# SingleDriver.net
KiCad netlist of a schematic drawn in Altium Designer
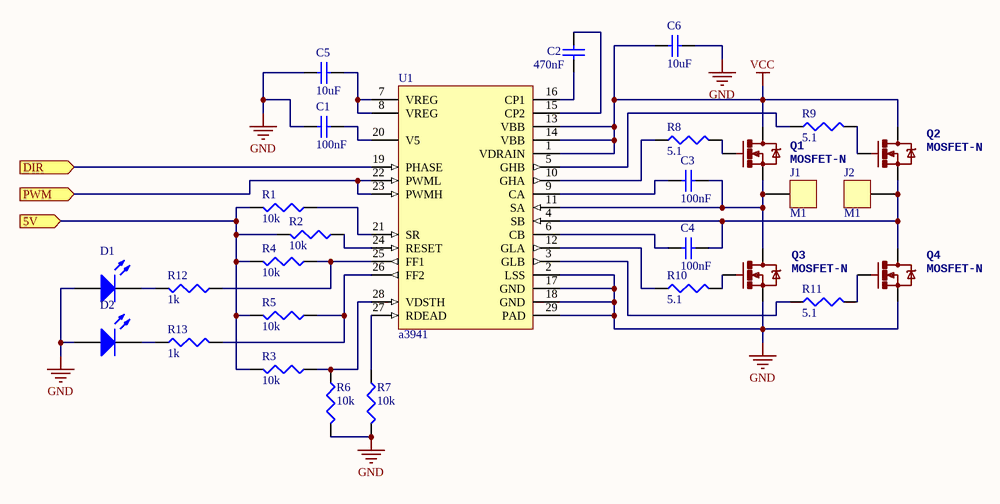
[diagram p0: SingleDriver.SchDoc]

(export (version "E")
  (design (tool "Eeschema 10.0.6"))
  (components
    (comp (ref "C1")
      (value "100nF")
      (footprint "1608[0603]")
      (description "Capacitor (Semiconductor SIM Model)")
      (fields (field (name "PUBLISHER") "Altium Limited"))
      (libsource (lib "Miscellaneous Devices") (part "Cap Semi"))
    )
    (comp (ref "C2")
      (value "470nF")
      (footprint "1608[0603]")
      (description "Capacitor (Semiconductor SIM Model)")
      (fields (field (name "PUBLISHER") "Altium Limited"))
      (libsource (lib "Miscellaneous Devices") (part "Cap Semi"))
    )
    (comp (ref "C3")
      (value "100nF")
      (footprint "1608[0603]")
      (description "Capacitor (Semiconductor SIM Model)")
      (fields (field (name "PUBLISHER") "Altium Limited"))
      (libsource (lib "Miscellaneous Devices") (part "Cap Semi"))
    )
    (comp (ref "C4")
      (value "100nF")
      (footprint "1608[0603]")
      (description "Capacitor (Semiconductor SIM Model)")
      (fields (field (name "PUBLISHER") "Altium Limited"))
      (libsource (lib "Miscellaneous Devices") (part "Cap Semi"))
    )
    (comp (ref "C5")
      (value "10uF")
      (footprint "C1206")
      (description "Capacitor (Semiconductor SIM Model)")
      (fields (field (name "PUBLISHER") "Altium Limited"))
      (libsource (lib "Miscellaneous Devices") (part "Cap Semi"))
    )
    (comp (ref "C6")
      (value "10uF")
      (footprint "C1206")
      (description "Capacitor (Semiconductor SIM Model)")
      (fields (field (name "PUBLISHER") "Altium Limited"))
      (libsource (lib "Miscellaneous Devices") (part "Cap Semi"))
    )
    (comp (ref "D1")
      (value "LED2")
      (footprint "1608[0603]")
      (description "Typical RED, GREEN, YELLOW, AMBER GaAs LED")
      (fields (field (name "PUBLISHER") "Altium Limited"))
      (libsource (lib "Miscellaneous Devices") (part "LED2"))
    )
    (comp (ref "D2")
      (value "LED2")
      (footprint "1608[0603]")
      (description "Typical RED, GREEN, YELLOW, AMBER GaAs LED")
      (fields (field (name "PUBLISHER") "Altium Limited"))
      (libsource (lib "Miscellaneous Devices") (part "LED2"))
    )
    (comp (ref "J1") (value "M1") (footprint "POWER-VIA") (libsource (lib "connectors") (part "HEADER-1")))
    (comp (ref "J2") (value "M1") (footprint "POWER-VIA") (libsource (lib "") (part "HEADER-1_1")))
    (comp (ref "Q1") (value "MOSFET-N") (footprint "SOT669") (libsource (lib "mosfets") (part "MOSFET-N")))
    (comp (ref "Q2") (value "MOSFET-N") (footprint "SOT669") (libsource (lib "mosfets") (part "MOSFET-N")))
    (comp (ref "Q3") (value "MOSFET-N") (footprint "SOT669") (libsource (lib "mosfets") (part "MOSFET-N")))
    (comp (ref "Q4") (value "MOSFET-N") (footprint "SOT669") (libsource (lib "mosfets") (part "MOSFET-N")))
    (comp (ref "R1")
      (value "10k")
      (footprint "J1-0603")
      (description "Resistor")
      (fields (field (name "PUBLISHER") "Altium Limited"))
      (libsource (lib "Miscellaneous Devices") (part "Res3"))
    )
    (comp (ref "R2")
      (value "10k")
      (footprint "J1-0603")
      (description "Resistor")
      (fields (field (name "PUBLISHER") "Altium Limited"))
      (libsource (lib "Miscellaneous Devices") (part "Res3"))
    )
    (comp (ref "R3")
      (value "10k")
      (footprint "J1-0603")
      (description "Resistor")
      (fields (field (name "PUBLISHER") "Altium Limited"))
      (libsource (lib "Miscellaneous Devices") (part "Res3"))
    )
    (comp (ref "R4")
      (value "10k")
      (footprint "J1-0603")
      (description "Resistor")
      (fields (field (name "PUBLISHER") "Altium Limited"))
      (libsource (lib "Miscellaneous Devices") (part "Res3"))
    )
    (comp (ref "R5")
      (value "10k")
      (footprint "J1-0603")
      (description "Resistor")
      (fields (field (name "PUBLISHER") "Altium Limited"))
      (libsource (lib "Miscellaneous Devices") (part "Res3"))
    )
    (comp (ref "R6")
      (value "10k")
      (footprint "J1-0603")
      (description "Resistor")
      (fields (field (name "PUBLISHER") "Altium Limited"))
      (libsource (lib "Miscellaneous Devices") (part "Res3"))
    )
    (comp (ref "R7")
      (value "10k")
      (footprint "J1-0603")
      (description "Resistor")
      (fields (field (name "PUBLISHER") "Altium Limited"))
      (libsource (lib "Miscellaneous Devices") (part "Res3"))
    )
    (comp (ref "R8")
      (value "5.1")
      (footprint "J1-0603")
      (description "Resistor")
      (fields (field (name "PUBLISHER") "Altium Limited"))
      (libsource (lib "Miscellaneous Devices") (part "Res3"))
    )
    (comp (ref "R9")
      (value "5.1")
      (footprint "J1-0603")
      (description "Resistor")
      (fields (field (name "PUBLISHER") "Altium Limited"))
      (libsource (lib "Miscellaneous Devices") (part "Res3"))
    )
    (comp (ref "R10")
      (value "5.1")
      (footprint "J1-0603")
      (description "Resistor")
      (fields (field (name "PUBLISHER") "Altium Limited"))
      (libsource (lib "Miscellaneous Devices") (part "Res3"))
    )
    (comp (ref "R11")
      (value "5.1")
      (footprint "J1-0603")
      (description "Resistor")
      (fields (field (name "PUBLISHER") "Altium Limited"))
      (libsource (lib "Miscellaneous Devices") (part "Res3"))
    )
    (comp (ref "R12")
      (value "1k")
      (footprint "J1-0603")
      (description "Resistor")
      (fields (field (name "PUBLISHER") "Altium Limited"))
      (libsource (lib "Miscellaneous Devices") (part "Res3"))
    )
    (comp (ref "R13")
      (value "1k")
      (footprint "J1-0603")
      (description "Resistor")
      (fields (field (name "PUBLISHER") "Altium Limited"))
      (libsource (lib "Miscellaneous Devices") (part "Res3"))
    )
    (comp (ref "U1") (value "a3941") (footprint "TSSOP28") (libsource (lib "allegro") (part "a3941")))
  )
  (nets
    (net (code "1") (name "/5V") (class "Default")
      (node (ref "R1") (pin "2") (pinfunction "2_2") (pintype "passive"))
      (node (ref "R2") (pin "2") (pinfunction "2_2") (pintype "passive"))
      (node (ref "R3") (pin "2") (pinfunction "2_2") (pintype "passive"))
      (node (ref "R4") (pin "2") (pinfunction "2_2") (pintype "passive"))
      (node (ref "R5") (pin "2") (pinfunction "2_2") (pintype "passive"))
    )
    (net (code "2") (name "/DIR") (class "Default")
      (node (ref "U1") (pin "19") (pinfunction "PHASE_19") (pintype "input"))
    )
    (net (code "3") (name "/PWM") (class "Default")
      (node (ref "U1") (pin "22") (pinfunction "PWML_22") (pintype "input"))
      (node (ref "U1") (pin "23") (pinfunction "PWMH_23") (pintype "input"))
    )
    (net (code "4") (name "GND") (class "Default")
      (node (ref "C1") (pin "1") (pinfunction "1_1") (pintype "passive"))
      (node (ref "C5") (pin "1") (pinfunction "1_1") (pintype "passive"))
      (node (ref "C6") (pin "2") (pinfunction "2_2") (pintype "passive"))
      (node (ref "D1") (pin "1") (pinfunction "A_1") (pintype "passive"))
      (node (ref "D2") (pin "1") (pinfunction "A_1") (pintype "passive"))
      (node (ref "Q3") (pin "S") (pinfunction "S_S") (pintype "passive"))
      (node (ref "Q4") (pin "S") (pinfunction "S_S") (pintype "passive"))
      (node (ref "R6") (pin "2") (pinfunction "2_2") (pintype "passive"))
      (node (ref "R7") (pin "2") (pinfunction "2_2") (pintype "passive"))
      (node (ref "U1") (pin "17") (pinfunction "GND_17") (pintype "power_in"))
      (node (ref "U1") (pin "18") (pinfunction "GND_18") (pintype "power_in"))
      (node (ref "U1") (pin "2") (pinfunction "LSS_2") (pintype "power_in"))
      (node (ref "U1") (pin "29") (pinfunction "PAD_29") (pintype "power_in"))
    )
    (net (code "5") (name "Net-(C5-Pad2)") (class "Default")
      (node (ref "C5") (pin "2") (pinfunction "2_2") (pintype "passive"))
      (node (ref "U1") (pin "7") (pinfunction "VREG_7") (pintype "power_in"))
      (node (ref "U1") (pin "8") (pinfunction "VREG_8") (pintype "power_in"))
    )
    (net (code "6") (name "Net-(D1-K)") (class "Default")
      (node (ref "D1") (pin "2") (pinfunction "K_2") (pintype "passive"))
      (node (ref "R12") (pin "2") (pinfunction "2_2") (pintype "passive"))
    )
    (net (code "7") (name "Net-(D2-K)") (class "Default")
      (node (ref "D2") (pin "2") (pinfunction "K_2") (pintype "passive"))
      (node (ref "R13") (pin "1") (pinfunction "1_1") (pintype "passive"))
    )
    (net (code "8") (name "Net-(Q1-PadG)") (class "Default")
      (node (ref "Q1") (pin "G") (pinfunction "G_G") (pintype "passive"))
      (node (ref "R8") (pin "2") (pinfunction "2_2") (pintype "passive"))
    )
    (net (code "9") (name "Net-(Q2-PadG)") (class "Default")
      (node (ref "Q2") (pin "G") (pinfunction "G_G") (pintype "passive"))
      (node (ref "R9") (pin "2") (pinfunction "2_2") (pintype "passive"))
    )
    (net (code "10") (name "Net-(Q3-PadG)") (class "Default")
      (node (ref "Q3") (pin "G") (pinfunction "G_G") (pintype "passive"))
      (node (ref "R10") (pin "2") (pinfunction "2_2") (pintype "passive"))
    )
    (net (code "11") (name "Net-(Q4-PadG)") (class "Default")
      (node (ref "Q4") (pin "G") (pinfunction "G_G") (pintype "passive"))
      (node (ref "R11") (pin "2") (pinfunction "2_2") (pintype "passive"))
    )
    (net (code "12") (name "Net-(U1-CA)") (class "Default")
      (node (ref "C3") (pin "1") (pinfunction "1_1") (pintype "passive"))
      (node (ref "U1") (pin "9") (pinfunction "CA_9") (pintype "power_in"))
    )
    (net (code "13") (name "Net-(U1-CB)") (class "Default")
      (node (ref "C4") (pin "1") (pinfunction "1_1") (pintype "passive"))
      (node (ref "U1") (pin "6") (pinfunction "CB_6") (pintype "power_in"))
    )
    (net (code "14") (name "Net-(U1-CP1)") (class "Default")
      (node (ref "C2") (pin "1") (pinfunction "1_1") (pintype "passive"))
      (node (ref "U1") (pin "16") (pinfunction "CP1_16") (pintype "power_in"))
    )
    (net (code "15") (name "Net-(U1-CP2)") (class "Default")
      (node (ref "C2") (pin "2") (pinfunction "2_2") (pintype "passive"))
      (node (ref "U1") (pin "15") (pinfunction "CP2_15") (pintype "power_in"))
    )
    (net (code "16") (name "Net-(U1-FF1)") (class "Default")
      (node (ref "R12") (pin "1") (pinfunction "1_1") (pintype "passive"))
      (node (ref "R4") (pin "1") (pinfunction "1_1") (pintype "passive"))
      (node (ref "U1") (pin "25") (pinfunction "FF1_25") (pintype "output"))
    )
    (net (code "17") (name "Net-(U1-FF2)") (class "Default")
      (node (ref "R13") (pin "2") (pinfunction "2_2") (pintype "passive"))
      (node (ref "R5") (pin "1") (pinfunction "1_1") (pintype "passive"))
      (node (ref "U1") (pin "26") (pinfunction "FF2_26") (pintype "output"))
    )
    (net (code "18") (name "Net-(U1-GHA)") (class "Default")
      (node (ref "R8") (pin "1") (pinfunction "1_1") (pintype "passive"))
      (node (ref "U1") (pin "10") (pinfunction "GHA_10") (pintype "output"))
    )
    (net (code "19") (name "Net-(U1-GHB)") (class "Default")
      (node (ref "R9") (pin "1") (pinfunction "1_1") (pintype "passive"))
      (node (ref "U1") (pin "5") (pinfunction "GHB_5") (pintype "output"))
    )
    (net (code "20") (name "Net-(U1-GLA)") (class "Default")
      (node (ref "R10") (pin "1") (pinfunction "1_1") (pintype "passive"))
      (node (ref "U1") (pin "12") (pinfunction "GLA_12") (pintype "output"))
    )
    (net (code "21") (name "Net-(U1-GLB)") (class "Default")
      (node (ref "R11") (pin "1") (pinfunction "1_1") (pintype "passive"))
      (node (ref "U1") (pin "3") (pinfunction "GLB_3") (pintype "output"))
    )
    (net (code "22") (name "Net-(U1-RDEAD)") (class "Default")
      (node (ref "R7") (pin "1") (pinfunction "1_1") (pintype "passive"))
      (node (ref "U1") (pin "27") (pinfunction "RDEAD_27") (pintype "input"))
    )
    (net (code "23") (name "Net-(U1-RESET)") (class "Default")
      (node (ref "R2") (pin "1") (pinfunction "1_1") (pintype "passive"))
      (node (ref "U1") (pin "24") (pinfunction "RESET_24") (pintype "input"))
    )
    (net (code "24") (name "Net-(U1-SA)") (class "Default")
      (node (ref "C3") (pin "2") (pinfunction "2_2") (pintype "passive"))
      (node (ref "J1") (pin "1") (pinfunction "1_1") (pintype "passive"))
      (node (ref "Q1") (pin "S") (pinfunction "S_S") (pintype "passive"))
      (node (ref "Q3") (pin "D") (pinfunction "D_D") (pintype "passive"))
      (node (ref "U1") (pin "11") (pinfunction "SA_11") (pintype "input"))
    )
    (net (code "25") (name "Net-(U1-SB)") (class "Default")
      (node (ref "C4") (pin "2") (pinfunction "2_2") (pintype "passive"))
      (node (ref "J2") (pin "1") (pinfunction "1_1") (pintype "passive"))
      (node (ref "Q2") (pin "S") (pinfunction "S_S") (pintype "passive"))
      (node (ref "Q4") (pin "D") (pinfunction "D_D") (pintype "passive"))
      (node (ref "U1") (pin "4") (pinfunction "SB_4") (pintype "input"))
    )
    (net (code "26") (name "Net-(U1-SR)") (class "Default")
      (node (ref "R1") (pin "1") (pinfunction "1_1") (pintype "passive"))
      (node (ref "U1") (pin "21") (pinfunction "SR_21") (pintype "input"))
    )
    (net (code "27") (name "Net-(U1-V5)") (class "Default")
      (node (ref "C1") (pin "2") (pinfunction "2_2") (pintype "passive"))
      (node (ref "U1") (pin "20") (pinfunction "V5_20") (pintype "power_in"))
    )
    (net (code "28") (name "Net-(U1-VDSTH)") (class "Default")
      (node (ref "R3") (pin "1") (pinfunction "1_1") (pintype "passive"))
      (node (ref "R6") (pin "1") (pinfunction "1_1") (pintype "passive"))
      (node (ref "U1") (pin "28") (pinfunction "VDSTH_28") (pintype "input"))
    )
    (net (code "29") (name "VCC") (class "Default")
      (node (ref "C6") (pin "1") (pinfunction "1_1") (pintype "passive"))
      (node (ref "Q1") (pin "D") (pinfunction "D_D") (pintype "passive"))
      (node (ref "Q2") (pin "D") (pinfunction "D_D") (pintype "passive"))
      (node (ref "U1") (pin "1") (pinfunction "VDRAIN_1") (pintype "power_in"))
      (node (ref "U1") (pin "13") (pinfunction "VBB_13") (pintype "power_in"))
      (node (ref "U1") (pin "14") (pinfunction "VBB_14") (pintype "power_in"))
    )
  )
)
